# 230V_Inputs.net
KiCad netlist of a schematic drawn in Altium Designer
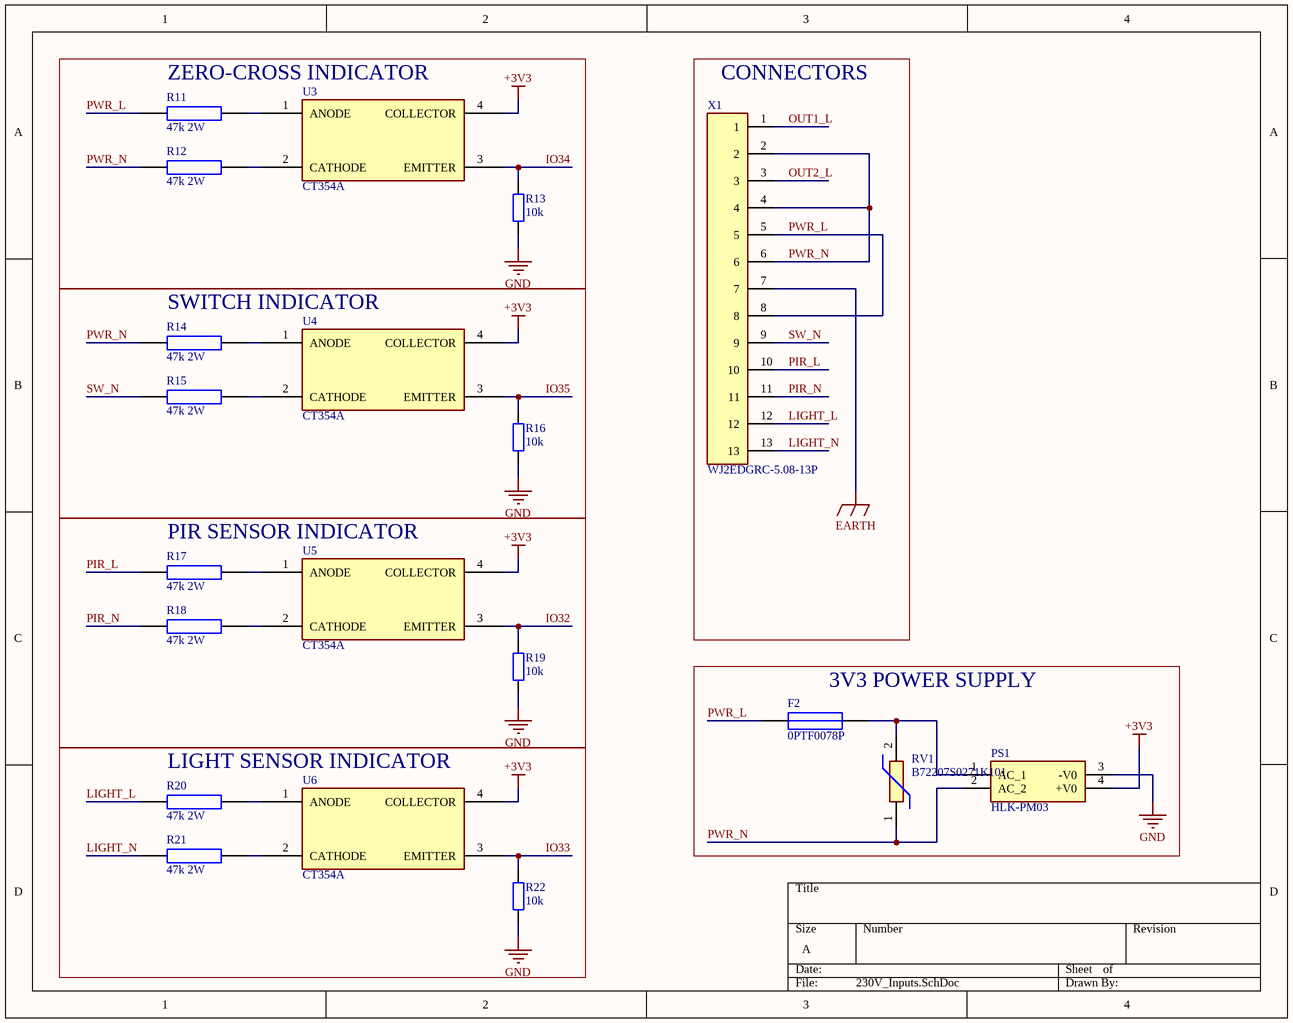
[diagram p0: 230V_Inputs.SchDoc]

(export (version "E")
  (design (tool "Eeschema 10.0.6"))
  (components
    (comp (ref "F2")
      (value "0PTF0078P")
      (footprint "FH1-200CK-B")
      (description "Fuse holder")
      (fields (field (name "MOUSER PART NUMBER") "576-0PTF0078P"))
      (libsource (lib "SamacSys") (part "0PTF0078P"))
    )
    (comp (ref "PS1")
      (value "HLK-PM03")
      (footprint "SamacSys:HLKPM03")
      (description "Power Supply")
      (libsource (lib "*") (part "HLK-PM03"))
    )
    (comp (ref "R11")
      (value "47k 2W")
      (footprint "MFR02SF4702A10")
      (description "MFR02SF4702A10")
      (libsource (lib "SamacSys") (part "47k 2W resistor"))
    )
    (comp (ref "R12")
      (value "47k 2W")
      (footprint "MFR02SF4702A10")
      (description "MFR02SF4702A10")
      (libsource (lib "SamacSys") (part "47k 2W resistor"))
    )
    (comp (ref "R13")
      (value "10k")
      (footprint "R2012_0805I_N")
      (description "R")
      (libsource (lib "General") (part "R"))
    )
    (comp (ref "R14")
      (value "47k 2W")
      (footprint "MFR02SF4702A10")
      (description "MFR02SF4702A10")
      (libsource (lib "SamacSys") (part "47k 2W resistor"))
    )
    (comp (ref "R15")
      (value "47k 2W")
      (footprint "MFR02SF4702A10")
      (description "MFR02SF4702A10")
      (libsource (lib "SamacSys") (part "47k 2W resistor"))
    )
    (comp (ref "R16")
      (value "10k")
      (footprint "R2012_0805I_N")
      (description "R")
      (libsource (lib "General") (part "R"))
    )
    (comp (ref "R17")
      (value "47k 2W")
      (footprint "MFR02SF4702A10")
      (description "MFR02SF4702A10")
      (libsource (lib "SamacSys") (part "47k 2W resistor"))
    )
    (comp (ref "R18")
      (value "47k 2W")
      (footprint "MFR02SF4702A10")
      (description "MFR02SF4702A10")
      (libsource (lib "SamacSys") (part "47k 2W resistor"))
    )
    (comp (ref "R19")
      (value "10k")
      (footprint "R2012_0805I_N")
      (description "R")
      (libsource (lib "General") (part "R"))
    )
    (comp (ref "R20")
      (value "47k 2W")
      (footprint "MFR02SF4702A10")
      (description "MFR02SF4702A10")
      (libsource (lib "SamacSys") (part "47k 2W resistor"))
    )
    (comp (ref "R21")
      (value "47k 2W")
      (footprint "MFR02SF4702A10")
      (description "MFR02SF4702A10")
      (libsource (lib "SamacSys") (part "47k 2W resistor"))
    )
    (comp (ref "R22")
      (value "10k")
      (footprint "R2012_0805I_N")
      (description "R")
      (libsource (lib "General") (part "R"))
    )
    (comp (ref "RV1")
      (value "B72207S0271K101")
      (footprint "SamacSys:B72207S0271K101")
      (description "Varistor")
      (fields (field (name "MOUSER PART NUMBER") "871-B72207S271K101"))
      (libsource (lib "SamacSys") (part "B72207S0271K101"))
    )
    (comp (ref "U3") (value "CT354A") (footprint "CT354A") (libsource (lib "SamacSys") (part "CT354A")))
    (comp (ref "U4") (value "CT354A") (footprint "CT354A") (libsource (lib "SamacSys") (part "CT354A")))
    (comp (ref "U5") (value "CT354A") (footprint "CT354A") (libsource (lib "SamacSys") (part "CT354A")))
    (comp (ref "U6") (value "CT354A") (footprint "CT354A") (libsource (lib "SamacSys") (part "CT354A")))
    (comp (ref "X1")
      (value "WJ2EDGRC-5.08-13P")
      (footprint "WJ2EDGRC-5.08-13P_SLIM")
      (description "13P 5.08 mm female socket connector")
      (libsource (lib "SamacSys") (part "WJ2EDGRC-5.08-13P"))
    )
  )
  (nets
    (net (code "1") (name "+3V3") (class "Default")
      (node (ref "PS1") (pin "4") (pinfunction "+V0_4") (pintype "passive"))
      (node (ref "U3") (pin "4") (pinfunction "COLLECTOR_4") (pintype "passive"))
      (node (ref "U4") (pin "4") (pinfunction "COLLECTOR_4") (pintype "passive"))
      (node (ref "U5") (pin "4") (pinfunction "COLLECTOR_4") (pintype "passive"))
      (node (ref "U6") (pin "4") (pinfunction "COLLECTOR_4") (pintype "passive"))
    )
    (net (code "2") (name "/IO32") (class "Default")
      (node (ref "R19") (pin "2") (pintype "passive"))
      (node (ref "U5") (pin "3") (pinfunction "EMITTER_3") (pintype "passive"))
    )
    (net (code "3") (name "/IO33") (class "Default")
      (node (ref "R22") (pin "2") (pintype "passive"))
      (node (ref "U6") (pin "3") (pinfunction "EMITTER_3") (pintype "passive"))
    )
    (net (code "4") (name "/IO34") (class "Default")
      (node (ref "R13") (pin "2") (pintype "passive"))
      (node (ref "U3") (pin "3") (pinfunction "EMITTER_3") (pintype "passive"))
    )
    (net (code "5") (name "/IO35") (class "Default")
      (node (ref "R16") (pin "2") (pintype "passive"))
      (node (ref "U4") (pin "3") (pinfunction "EMITTER_3") (pintype "passive"))
    )
    (net (code "6") (name "/LIGHT_L") (class "Default")
      (node (ref "R20") (pin "1") (pintype "passive"))
      (node (ref "X1") (pin "12") (pinfunction "12_12") (pintype "passive"))
    )
    (net (code "7") (name "/LIGHT_N") (class "Default")
      (node (ref "R21") (pin "1") (pintype "passive"))
      (node (ref "X1") (pin "13") (pinfunction "13_13") (pintype "passive"))
    )
    (net (code "8") (name "/OUT1_L") (class "Default")
      (node (ref "X1") (pin "1") (pinfunction "1_1") (pintype "passive"))
    )
    (net (code "9") (name "/OUT2_L") (class "Default")
      (node (ref "X1") (pin "3") (pinfunction "3_3") (pintype "passive"))
    )
    (net (code "10") (name "/PIR_L") (class "Default")
      (node (ref "R17") (pin "1") (pintype "passive"))
      (node (ref "X1") (pin "10") (pinfunction "10_10") (pintype "passive"))
    )
    (net (code "11") (name "/PIR_N") (class "Default")
      (node (ref "R18") (pin "1") (pintype "passive"))
      (node (ref "X1") (pin "11") (pinfunction "11_11") (pintype "passive"))
    )
    (net (code "12") (name "/PWR_L") (class "Default")
      (node (ref "F2") (pin "1") (pintype "passive"))
      (node (ref "R11") (pin "1") (pintype "passive"))
      (node (ref "X1") (pin "5") (pinfunction "5_5") (pintype "passive"))
      (node (ref "X1") (pin "8") (pinfunction "8_8") (pintype "passive"))
    )
    (net (code "13") (name "/PWR_N") (class "Default")
      (node (ref "PS1") (pin "2") (pinfunction "AC_2_2") (pintype "passive"))
      (node (ref "R12") (pin "1") (pintype "passive"))
      (node (ref "R14") (pin "1") (pintype "passive"))
      (node (ref "RV1") (pin "1") (pinfunction "1_1") (pintype "passive"))
      (node (ref "X1") (pin "2") (pinfunction "2_2") (pintype "passive"))
      (node (ref "X1") (pin "4") (pinfunction "4_4") (pintype "passive"))
      (node (ref "X1") (pin "6") (pinfunction "6_6") (pintype "passive"))
    )
    (net (code "14") (name "/SW_N") (class "Default")
      (node (ref "R15") (pin "1") (pintype "passive"))
      (node (ref "X1") (pin "9") (pinfunction "9_9") (pintype "passive"))
    )
    (net (code "15") (name "EARTH") (class "Default")
      (node (ref "X1") (pin "7") (pinfunction "7_7") (pintype "passive"))
    )
    (net (code "16") (name "GND") (class "Default")
      (node (ref "PS1") (pin "3") (pinfunction "-V0_3") (pintype "passive"))
      (node (ref "R13") (pin "1") (pintype "passive"))
      (node (ref "R16") (pin "1") (pintype "passive"))
      (node (ref "R19") (pin "1") (pintype "passive"))
      (node (ref "R22") (pin "1") (pintype "passive"))
    )
    (net (code "17") (name "Net-(PS1-AC_1)") (class "Default")
      (node (ref "F2") (pin "2") (pintype "passive"))
      (node (ref "PS1") (pin "1") (pinfunction "AC_1_1") (pintype "passive"))
      (node (ref "RV1") (pin "2") (pinfunction "2_2") (pintype "passive"))
    )
    (net (code "18") (name "Net-(U3-ANODE)") (class "Default")
      (node (ref "R11") (pin "2") (pintype "passive"))
      (node (ref "U3") (pin "1") (pinfunction "ANODE_1") (pintype "passive"))
    )
    (net (code "19") (name "Net-(U3-CATHODE)") (class "Default")
      (node (ref "R12") (pin "2") (pintype "passive"))
      (node (ref "U3") (pin "2") (pinfunction "CATHODE_2") (pintype "passive"))
    )
    (net (code "20") (name "Net-(U4-ANODE)") (class "Default")
      (node (ref "R14") (pin "2") (pintype "passive"))
      (node (ref "U4") (pin "1") (pinfunction "ANODE_1") (pintype "passive"))
    )
    (net (code "21") (name "Net-(U4-CATHODE)") (class "Default")
      (node (ref "R15") (pin "2") (pintype "passive"))
      (node (ref "U4") (pin "2") (pinfunction "CATHODE_2") (pintype "passive"))
    )
    (net (code "22") (name "Net-(U5-ANODE)") (class "Default")
      (node (ref "R17") (pin "2") (pintype "passive"))
      (node (ref "U5") (pin "1") (pinfunction "ANODE_1") (pintype "passive"))
    )
    (net (code "23") (name "Net-(U5-CATHODE)") (class "Default")
      (node (ref "R18") (pin "2") (pintype "passive"))
      (node (ref "U5") (pin "2") (pinfunction "CATHODE_2") (pintype "passive"))
    )
    (net (code "24") (name "Net-(U6-ANODE)") (class "Default")
      (node (ref "R20") (pin "2") (pintype "passive"))
      (node (ref "U6") (pin "1") (pinfunction "ANODE_1") (pintype "passive"))
    )
    (net (code "25") (name "Net-(U6-CATHODE)") (class "Default")
      (node (ref "R21") (pin "2") (pintype "passive"))
      (node (ref "U6") (pin "2") (pinfunction "CATHODE_2") (pintype "passive"))
    )
  )
)
